# TLE8209-2SA.net
KiCad netlist of a schematic drawn in Altium Designer
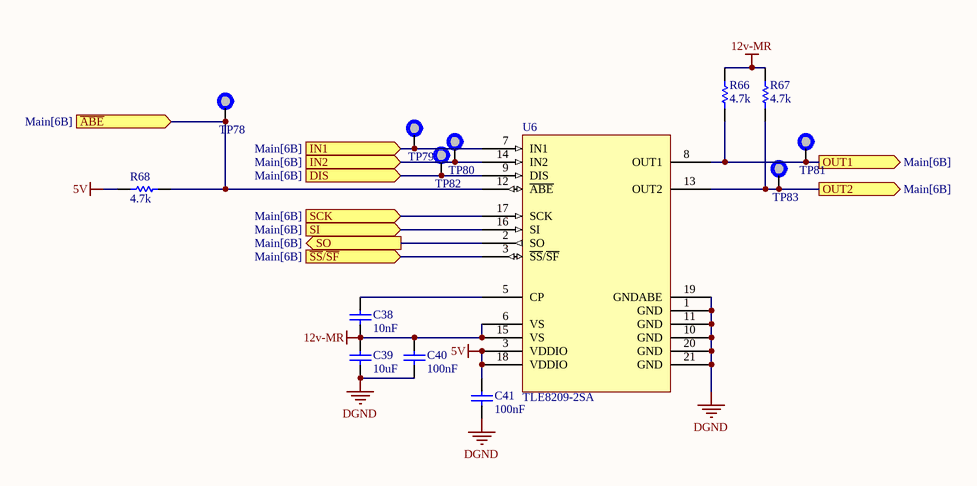
[diagram p0: TLE8209-2SA.SchDoc]

(export (version "E")
  (design (tool "Eeschema 10.0.6"))
  (components
    (comp (ref "C38")
      (value "10nF")
      (footprint "0603C")
      (description "Capacitor")
      (fields (field (name "Comment") "CGA3E2X7R1H104K080AA") (field (name "PUBLISHER") "Altium Limited"))
      (libsource (lib "Miscellaneous Devices") (part "Cap"))
    )
    (comp (ref "C39")
      (value "10uF")
      (footprint "0805C")
      (description "Capacitor")
      (fields (field (name "Comment") "CGA3E2X7R1H104K080AA") (field (name "PUBLISHER") "Altium Limited"))
      (libsource (lib "Miscellaneous Devices") (part "Cap"))
    )
    (comp (ref "C40")
      (value "100nF")
      (footprint "0603C")
      (description "Capacitor")
      (fields (field (name "Comment") "CGA3E2X7R1H104K080AA") (field (name "PUBLISHER") "Altium Limited"))
      (libsource (lib "Miscellaneous Devices") (part "Cap"))
    )
    (comp (ref "C41")
      (value "100nF")
      (footprint "0603C")
      (description "Capacitor")
      (fields (field (name "Comment") "CGA3E2X7R1H104K080AA") (field (name "PUBLISHER") "Altium Limited"))
      (libsource (lib "Miscellaneous Devices") (part "Cap"))
    )
    (comp (ref "R66")
      (value "4.7k")
      (footprint "1206")
      (description "Resistor")
      (fields (field (name "Comment") "Res1") (field (name "PUBLISHER") "Altium Limited"))
      (libsource (lib "Miscellaneous Devices") (part "Res1"))
    )
    (comp (ref "R67")
      (value "4.7k")
      (footprint "1206")
      (description "Resistor")
      (fields (field (name "Comment") "Res1") (field (name "PUBLISHER") "Altium Limited"))
      (libsource (lib "Miscellaneous Devices") (part "Res1"))
    )
    (comp (ref "R68")
      (value "4.7k")
      (footprint "1206")
      (description "Resistor")
      (fields (field (name "Comment") "Res1") (field (name "PUBLISHER") "Altium Limited"))
      (libsource (lib "Miscellaneous Devices") (part "Res1"))
    )
    (comp (ref "TP78") (value "TestPoint") (footprint "TP") (libsource (lib "SchlibV0.1") (part "TestPoint")))
    (comp (ref "TP79") (value "TestPoint") (footprint "TP") (libsource (lib "SchlibV0.1") (part "TestPoint")))
    (comp (ref "TP80") (value "TestPoint") (footprint "TP") (libsource (lib "SchlibV0.1") (part "TestPoint")))
    (comp (ref "TP81") (value "TestPoint") (footprint "TP") (libsource (lib "SchlibV0.1") (part "TestPoint")))
    (comp (ref "TP82") (value "TestPoint") (footprint "TP") (libsource (lib "SchlibV0.1") (part "TestPoint")))
    (comp (ref "TP83") (value "TestPoint") (footprint "TP") (libsource (lib "SchlibV0.1") (part "TestPoint")))
    (comp (ref "U6")
      (value "TLE8209-2SA")
      (footprint "TLE8209-2SA")
      (libsource (lib "SchlibV0.1") (part "TLE8209-2SA"))
    )
  )
  (nets
    (net (code "1") (name "/DIS") (class "Default")
      (node (ref "TP82") (pin "1") (pintype "passive"))
      (node (ref "U6") (pin "9") (pinfunction "DIS_9") (pintype "input"))
    )
    (net (code "2") (name "/IN1") (class "Default")
      (node (ref "TP79") (pin "1") (pintype "passive"))
      (node (ref "U6") (pin "7") (pinfunction "IN1_7") (pintype "input"))
    )
    (net (code "3") (name "/IN2") (class "Default")
      (node (ref "TP80") (pin "1") (pintype "passive"))
      (node (ref "U6") (pin "14") (pinfunction "IN2_14") (pintype "input"))
    )
    (net (code "4") (name "/OUT1") (class "Default")
      (node (ref "R66") (pin "2") (pinfunction "2_2") (pintype "passive"))
      (node (ref "TP81") (pin "1") (pintype "passive"))
      (node (ref "U6") (pin "8") (pinfunction "OUT1_8") (pintype "passive"))
    )
    (net (code "5") (name "/OUT2") (class "Default")
      (node (ref "R67") (pin "2") (pinfunction "2_2") (pintype "passive"))
      (node (ref "TP83") (pin "1") (pintype "passive"))
      (node (ref "U6") (pin "13") (pinfunction "OUT2_13") (pintype "passive"))
    )
    (net (code "6") (name "/SCK") (class "Default")
      (node (ref "U6") (pin "17") (pinfunction "SCK_17") (pintype "input"))
    )
    (net (code "7") (name "/SI") (class "Default")
      (node (ref "U6") (pin "16") (pinfunction "SI_16") (pintype "input"))
    )
    (net (code "8") (name "/SO") (class "Default")
      (node (ref "U6") (pin "2") (pinfunction "SO_2") (pintype "output"))
    )
    (net (code "9") (name "/~{ABE}") (class "Default")
      (node (ref "R68") (pin "2") (pinfunction "2_2") (pintype "passive"))
      (node (ref "TP78") (pin "1") (pintype "passive"))
      (node (ref "U6") (pin "12") (pinfunction "~{ABE}_12") (pintype "bidirectional"))
    )
    (net (code "10") (name "/~{SS}{slash}~{SF}") (class "Default")
      (node (ref "U6") (pin "3") (pinfunction "~{SS}/~{SF}_3") (pintype "bidirectional"))
    )
    (net (code "11") (name "5V") (class "Default")
      (node (ref "C41") (pin "1") (pinfunction "1_1") (pintype "passive"))
      (node (ref "R68") (pin "1") (pinfunction "1_1") (pintype "passive"))
      (node (ref "U6") (pin "18") (pinfunction "VDDIO_18") (pintype "passive"))
      (node (ref "U6") (pin "3") (pinfunction "VDDIO_3") (pintype "passive"))
    )
    (net (code "12") (name "12v-MR") (class "Default")
      (node (ref "C38") (pin "2") (pinfunction "2_2") (pintype "passive"))
      (node (ref "C39") (pin "1") (pinfunction "1_1") (pintype "passive"))
      (node (ref "C40") (pin "1") (pinfunction "1_1") (pintype "passive"))
      (node (ref "R66") (pin "1") (pinfunction "1_1") (pintype "passive"))
      (node (ref "R67") (pin "1") (pinfunction "1_1") (pintype "passive"))
      (node (ref "U6") (pin "15") (pinfunction "VS_15") (pintype "passive"))
      (node (ref "U6") (pin "6") (pinfunction "VS_6") (pintype "passive"))
    )
    (net (code "13") (name "DGND") (class "Default")
      (node (ref "C39") (pin "2") (pinfunction "2_2") (pintype "passive"))
      (node (ref "C40") (pin "2") (pinfunction "2_2") (pintype "passive"))
      (node (ref "C41") (pin "2") (pinfunction "2_2") (pintype "passive"))
      (node (ref "U6") (pin "1") (pinfunction "GND_1") (pintype "passive"))
      (node (ref "U6") (pin "10") (pinfunction "GND_10") (pintype "passive"))
      (node (ref "U6") (pin "11") (pinfunction "GND_11") (pintype "passive"))
      (node (ref "U6") (pin "19") (pinfunction "GNDABE_19") (pintype "passive"))
      (node (ref "U6") (pin "20") (pinfunction "GND_20") (pintype "passive"))
      (node (ref "U6") (pin "21") (pinfunction "GND_21") (pintype "passive"))
    )
    (net (code "14") (name "Net-(U6-CP)") (class "Default")
      (node (ref "C38") (pin "1") (pinfunction "1_1") (pintype "passive"))
      (node (ref "U6") (pin "5") (pinfunction "CP_5") (pintype "passive"))
    )
  )
)
